# Ambulance_Signal.net
KiCad netlist of a schematic drawn in EAGLE
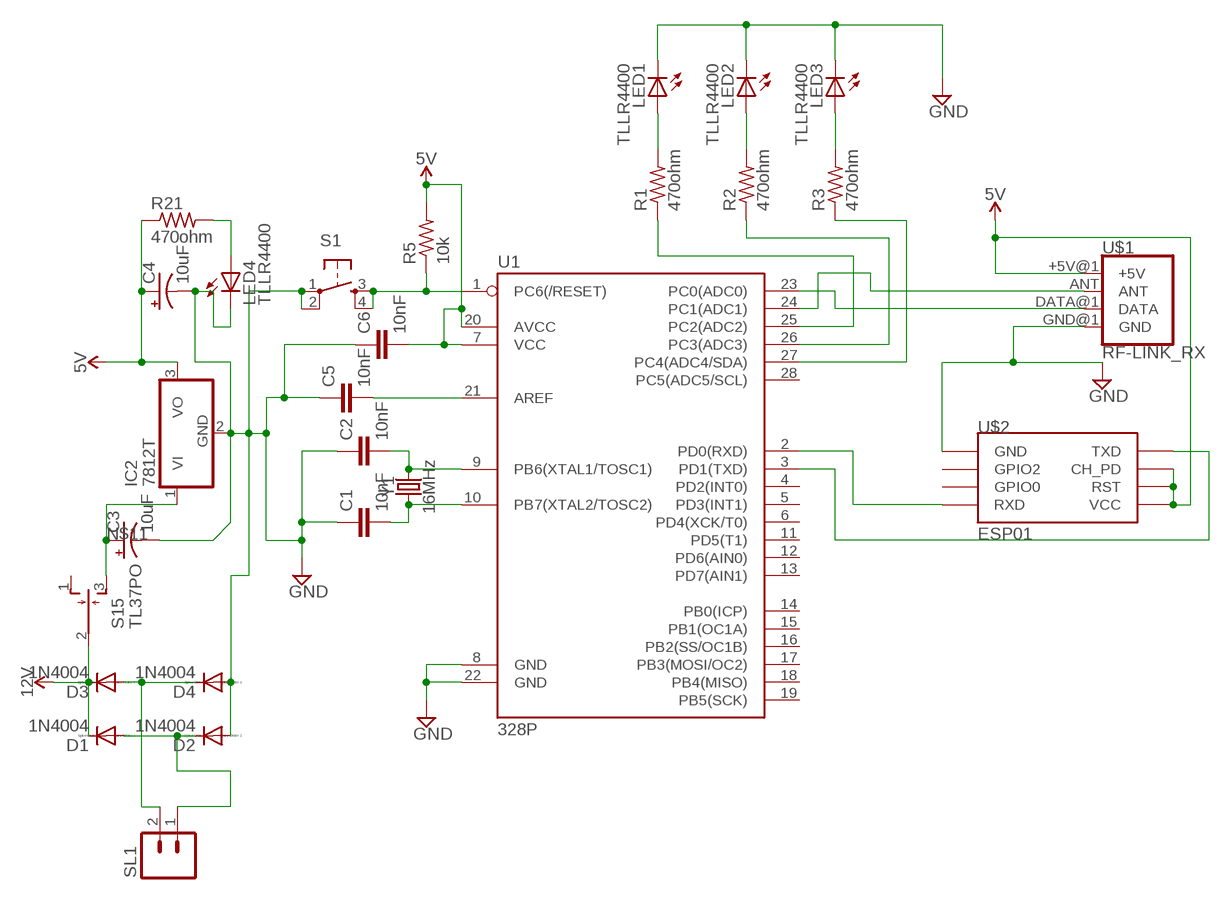
[diagram p0: schematic, sheet 1]

(export (version "E")
  (design (tool "Eeschema 10.0.6"))
  (components
    (comp (ref "C1")
      (value "10nF")
      (footprint "eagle-import:CAP-PTH-10MM")
      (libsource (lib "eagle-import") (part "10NF-PTH-10MM-10000V-1-%"))
    )
    (comp (ref "C2")
      (value "10nF")
      (footprint "eagle-import:CAP-PTH-10MM")
      (libsource (lib "eagle-import") (part "10NF-PTH-10MM-10000V-1-%"))
    )
    (comp (ref "C3")
      (value "10uF")
      (footprint "eagle-import:CPOL-RADIAL-2.5MM-5MM-KIT")
      (libsource (lib "eagle-import") (part "10UF-POLAR-RADIAL-2.5MM-KIT-25V-20%"))
    )
    (comp (ref "C4")
      (value "10uF")
      (footprint "eagle-import:CPOL-RADIAL-2.5MM-5MM-KIT")
      (libsource (lib "eagle-import") (part "10UF-POLAR-RADIAL-2.5MM-KIT-25V-20%"))
    )
    (comp (ref "C5")
      (value "10nF")
      (footprint "eagle-import:CAP-PTH-10MM")
      (libsource (lib "eagle-import") (part "10NF-PTH-10MM-10000V-1-%"))
    )
    (comp (ref "C6")
      (value "10nF")
      (footprint "eagle-import:CAP-PTH-10MM")
      (libsource (lib "eagle-import") (part "10NF-PTH-10MM-10000V-1-%"))
    )
    (comp (ref "D1")
      (value "1N4004")
      (footprint "eagle-import:DO41-10")
      (libsource (lib "eagle-import") (part "1N4004"))
    )
    (comp (ref "D2")
      (value "1N4004")
      (footprint "eagle-import:DO41-10")
      (libsource (lib "eagle-import") (part "1N4004"))
    )
    (comp (ref "D3")
      (value "1N4004")
      (footprint "eagle-import:DO41-10")
      (libsource (lib "eagle-import") (part "1N4004"))
    )
    (comp (ref "D4")
      (value "1N4004")
      (footprint "eagle-import:DO41-10")
      (libsource (lib "eagle-import") (part "1N4004"))
    )
    (comp (ref "IC2")
      (value "7812T")
      (footprint "eagle-import:TO220H")
      (libsource (lib "eagle-import") (part "78T12"))
    )
    (comp (ref "LED1")
      (value "TLLR4400")
      (footprint "eagle-import:LED3MM")
      (fields (field (name "MF") "VISHAY SEMICONDUCTOR"))
      (libsource (lib "eagle-import") (part "TLLR4400"))
    )
    (comp (ref "LED2")
      (value "TLLR4400")
      (footprint "eagle-import:LED3MM")
      (fields (field (name "MF") "VISHAY SEMICONDUCTOR"))
      (libsource (lib "eagle-import") (part "TLLR4400"))
    )
    (comp (ref "LED3")
      (value "TLLR4400")
      (footprint "eagle-import:LED3MM")
      (fields (field (name "MF") "VISHAY SEMICONDUCTOR"))
      (libsource (lib "eagle-import") (part "TLLR4400"))
    )
    (comp (ref "LED4")
      (value "TLLR4400")
      (footprint "eagle-import:LED3MM")
      (fields (field (name "MF") "VISHAY SEMICONDUCTOR"))
      (libsource (lib "eagle-import") (part "TLLR4400"))
    )
    (comp (ref "R1")
      (value "470ohm")
      (footprint "eagle-import:0207_12")
      (libsource (lib "eagle-import") (part "R-US_0207/12"))
    )
    (comp (ref "R2")
      (value "470ohm")
      (footprint "eagle-import:0207_12")
      (libsource (lib "eagle-import") (part "R-US_0207/12"))
    )
    (comp (ref "R3")
      (value "470ohm")
      (footprint "eagle-import:0207_12")
      (libsource (lib "eagle-import") (part "R-US_0207/12"))
    )
    (comp (ref "R5")
      (value "10k")
      (footprint "eagle-import:0207_12")
      (libsource (lib "eagle-import") (part "R-US_0207/12"))
    )
    (comp (ref "R21")
      (value "470ohm")
      (footprint "eagle-import:0207_12")
      (libsource (lib "eagle-import") (part "R-US_0207/12"))
    )
    (comp (ref "S1")
      (value "TAC_SWITCHPTH")
      (footprint "eagle-import:TACTILE-PTH")
      (libsource (lib "eagle-import") (part "TAC_SWITCHPTH"))
    )
    (comp (ref "S15")
      (value "TL37PO")
      (footprint "eagle-import:TL3XPO")
      (libsource (lib "eagle-import") (part "TL37PO"))
    )
    (comp (ref "SL1")
      (value "MA02")
      (footprint "eagle-import:02PA")
      (libsource (lib "eagle-import") (part "MA02"))
    )
    (comp (ref "U$1")
      (value "RF-LINK_RX")
      (footprint "eagle-import:RF-LINK_RX")
      (libsource (lib "eagle-import") (part "RF-LINK_RX"))
    )
    (comp (ref "U$2")
      (value "ESP01")
      (footprint "eagle-import:ESP01")
      (libsource (lib "eagle-import") (part "ESP01"))
    )
    (comp (ref "U1")
      (value "328P")
      (footprint "eagle-import:DIP28")
      (libsource (lib "eagle-import") (part "ATMEGA328P_PDIP"))
    )
    (comp (ref "Y1")
      (value "16MHz")
      (footprint "eagle-import:HC49US")
      (libsource (lib "eagle-import") (part "CRYSTAL-16MHZPTH-HC49US"))
    )
  )
  (nets
    (net (code "1") (name "/N$11") (class "Default")
      (node (ref "C3") (pin "1") (pinfunction "+_1") (pintype "passive"))
      (node (ref "IC2") (pin "1") (pinfunction "VI_1") (pintype "input"))
      (node (ref "S15") (pin "3") (pinfunction "S_3") (pintype "passive"))
    )
    (net (code "2") (name "5V") (class "Default")
      (node (ref "C4") (pin "1") (pinfunction "+_1") (pintype "passive"))
      (node (ref "C6") (pin "2") (pinfunction "2_2") (pintype "passive"))
      (node (ref "IC2") (pin "3") (pinfunction "VO_3") (pintype "passive"))
      (node (ref "R21") (pin "1") (pinfunction "1_1") (pintype "passive"))
      (node (ref "R5") (pin "2") (pinfunction "2_2") (pintype "passive"))
      (node (ref "U$1") (pin "+5V@1") (pinfunction "+5V_+5V@1") (pintype "power_in"))
      (node (ref "U$2") (pin "CH_PD") (pinfunction "CH_PD_CH_PD") (pintype "bidirectional"))
      (node (ref "U$2") (pin "RST") (pinfunction "RST_RST") (pintype "bidirectional"))
      (node (ref "U$2") (pin "VCC") (pinfunction "VCC_VCC") (pintype "bidirectional"))
      (node (ref "U1") (pin "20") (pinfunction "AVCC_20") (pintype "bidirectional"))
      (node (ref "U1") (pin "7") (pinfunction "VCC_7") (pintype "bidirectional"))
    )
    (net (code "3") (name "12V") (class "Default")
      (node (ref "D1") (pin "C") (pinfunction "C_C") (pintype "passive"))
      (node (ref "D3") (pin "C") (pinfunction "C_C") (pintype "passive"))
      (node (ref "S15") (pin "2") (pinfunction "P_2") (pintype "passive"))
    )
    (net (code "4") (name "GND") (class "Default")
      (node (ref "C1") (pin "1") (pinfunction "1_1") (pintype "passive"))
      (node (ref "C2") (pin "1") (pinfunction "1_1") (pintype "passive"))
      (node (ref "C3") (pin "2") (pinfunction "-_2") (pintype "passive"))
      (node (ref "C4") (pin "2") (pinfunction "-_2") (pintype "passive"))
      (node (ref "C5") (pin "1") (pinfunction "1_1") (pintype "passive"))
      (node (ref "C6") (pin "1") (pinfunction "1_1") (pintype "passive"))
      (node (ref "D2") (pin "A") (pinfunction "A_A") (pintype "passive"))
      (node (ref "D4") (pin "A") (pinfunction "A_A") (pintype "passive"))
      (node (ref "IC2") (pin "2") (pinfunction "GND_2") (pintype "passive"))
      (node (ref "LED1") (pin "K") (pinfunction "C_K") (pintype "passive"))
      (node (ref "LED2") (pin "K") (pinfunction "C_K") (pintype "passive"))
      (node (ref "LED3") (pin "K") (pinfunction "C_K") (pintype "passive"))
      (node (ref "LED4") (pin "K") (pinfunction "C_K") (pintype "passive"))
      (node (ref "S1") (pin "1") (pinfunction "1_1") (pintype "passive"))
      (node (ref "S1") (pin "2") (pinfunction "2_2") (pintype "passive"))
      (node (ref "U$1") (pin "GND@1") (pinfunction "GND_GND@1") (pintype "power_in"))
      (node (ref "U$2") (pin "GND") (pinfunction "GND_GND") (pintype "bidirectional"))
      (node (ref "U1") (pin "22") (pinfunction "GND_22") (pintype "bidirectional"))
      (node (ref "U1") (pin "8") (pinfunction "GND_8") (pintype "bidirectional"))
    )
    (net (code "5") (name "Net-(D1-PadA)") (class "Default")
      (node (ref "D1") (pin "A") (pinfunction "A_A") (pintype "passive"))
      (node (ref "D2") (pin "C") (pinfunction "C_C") (pintype "passive"))
      (node (ref "SL1") (pin "1") (pinfunction "1_1") (pintype "passive"))
    )
    (net (code "6") (name "Net-(D3-PadA)") (class "Default")
      (node (ref "D3") (pin "A") (pinfunction "A_A") (pintype "passive"))
      (node (ref "D4") (pin "C") (pinfunction "C_C") (pintype "passive"))
      (node (ref "SL1") (pin "2") (pinfunction "2_2") (pintype "passive"))
    )
    (net (code "7") (name "Net-(LED1-PadA)") (class "Default")
      (node (ref "LED1") (pin "A") (pinfunction "A_A") (pintype "passive"))
      (node (ref "R1") (pin "2") (pinfunction "2_2") (pintype "passive"))
    )
    (net (code "8") (name "Net-(LED2-PadA)") (class "Default")
      (node (ref "LED2") (pin "A") (pinfunction "A_A") (pintype "passive"))
      (node (ref "R2") (pin "2") (pinfunction "2_2") (pintype "passive"))
    )
    (net (code "9") (name "Net-(LED3-PadA)") (class "Default")
      (node (ref "LED3") (pin "A") (pinfunction "A_A") (pintype "passive"))
      (node (ref "R3") (pin "2") (pinfunction "2_2") (pintype "passive"))
    )
    (net (code "10") (name "Net-(LED4-PadA)") (class "Default")
      (node (ref "LED4") (pin "A") (pinfunction "A_A") (pintype "passive"))
      (node (ref "R21") (pin "2") (pinfunction "2_2") (pintype "passive"))
    )
    (net (code "11") (name "Net-(U$1-DATA)") (class "Default")
      (node (ref "U$1") (pin "DATA@1") (pinfunction "DATA_DATA@1") (pintype "input"))
      (node (ref "U1") (pin "23") (pinfunction "PC0(ADC0)_23") (pintype "bidirectional"))
    )
    (net (code "12") (name "Net-(U$2-RXD)") (class "Default")
      (node (ref "U$2") (pin "RX") (pinfunction "RXD_RX") (pintype "bidirectional"))
      (node (ref "U1") (pin "2") (pinfunction "PD0(RXD)_2") (pintype "bidirectional"))
    )
    (net (code "13") (name "Net-(U$2-TXD)") (class "Default")
      (node (ref "U$2") (pin "TX") (pinfunction "TXD_TX") (pintype "bidirectional"))
      (node (ref "U1") (pin "3") (pinfunction "PD1(TXD)_3") (pintype "bidirectional"))
    )
    (net (code "14") (name "Net-(U1-AREF)") (class "Default")
      (node (ref "C5") (pin "2") (pinfunction "2_2") (pintype "passive"))
      (node (ref "U1") (pin "21") (pinfunction "AREF_21") (pintype "bidirectional"))
    )
    (net (code "15") (name "Net-(U1-PB6(XTAL1{slash}TOSC1))") (class "Default")
      (node (ref "C2") (pin "2") (pinfunction "2_2") (pintype "passive"))
      (node (ref "U1") (pin "9") (pinfunction "PB6(XTAL1/TOSC1)_9") (pintype "bidirectional"))
      (node (ref "Y1") (pin "2") (pinfunction "2_2") (pintype "passive"))
    )
    (net (code "16") (name "Net-(U1-PB7(XTAL2{slash}TOSC2))") (class "Default")
      (node (ref "C1") (pin "2") (pinfunction "2_2") (pintype "passive"))
      (node (ref "U1") (pin "10") (pinfunction "PB7(XTAL2/TOSC2)_10") (pintype "bidirectional"))
      (node (ref "Y1") (pin "1") (pinfunction "1_1") (pintype "passive"))
    )
    (net (code "17") (name "Net-(U1-PC1(ADC1))") (class "Default")
      (node (ref "U$1") (pin "ANT") (pinfunction "ANT_ANT") (pintype "passive"))
      (node (ref "U1") (pin "24") (pinfunction "PC1(ADC1)_24") (pintype "bidirectional"))
    )
    (net (code "18") (name "Net-(U1-PC2(ADC2))") (class "Default")
      (node (ref "R1") (pin "1") (pinfunction "1_1") (pintype "passive"))
      (node (ref "U1") (pin "25") (pinfunction "PC2(ADC2)_25") (pintype "bidirectional"))
    )
    (net (code "19") (name "Net-(U1-PC3(ADC3))") (class "Default")
      (node (ref "R2") (pin "1") (pinfunction "1_1") (pintype "passive"))
      (node (ref "U1") (pin "26") (pinfunction "PC3(ADC3)_26") (pintype "bidirectional"))
    )
    (net (code "20") (name "Net-(U1-PC4(ADC4{slash}SDA))") (class "Default")
      (node (ref "R3") (pin "1") (pinfunction "1_1") (pintype "passive"))
      (node (ref "U1") (pin "27") (pinfunction "PC4(ADC4/SDA)_27") (pintype "bidirectional"))
    )
    (net (code "21") (name "Net-(U1-PC6({slash}RESET))") (class "Default")
      (node (ref "R5") (pin "1") (pinfunction "1_1") (pintype "passive"))
      (node (ref "S1") (pin "3") (pinfunction "3_3") (pintype "passive"))
      (node (ref "S1") (pin "4") (pinfunction "4_4") (pintype "passive"))
      (node (ref "U1") (pin "1") (pinfunction "PC6(/RESET)_1") (pintype "bidirectional"))
    )
    (net (code "22") (name "unconnected-(S15-O-Pad1)") (class "Default")
      (node (ref "S15") (pin "1") (pinfunction "O_1") (pintype "passive"))
    )
    (net (code "23") (name "unconnected-(U$2-PadGPIO0)") (class "Default")
      (node (ref "U$2") (pin "GPIO0") (pinfunction "GPIO0_GPIO0") (pintype "bidirectional"))
    )
    (net (code "24") (name "unconnected-(U$2-PadGPIO2)") (class "Default")
      (node (ref "U$2") (pin "GPIO2") (pinfunction "GPIO2_GPIO2") (pintype "bidirectional"))
    )
    (net (code "25") (name "unconnected-(U1-PB0(ICP)-Pad14)") (class "Default")
      (node (ref "U1") (pin "14") (pinfunction "PB0(ICP)_14") (pintype "bidirectional"))
    )
    (net (code "26") (name "unconnected-(U1-PB1(OC1A)-Pad15)") (class "Default")
      (node (ref "U1") (pin "15") (pinfunction "PB1(OC1A)_15") (pintype "bidirectional"))
    )
    (net (code "27") (name "unconnected-(U1-PB2(SS{slash}OC1B)-Pad16)") (class "Default")
      (node (ref "U1") (pin "16") (pinfunction "PB2(SS/OC1B)_16") (pintype "bidirectional"))
    )
    (net (code "28") (name "unconnected-(U1-PB3(MOSI{slash}OC2)-Pad17)") (class "Default")
      (node (ref "U1") (pin "17") (pinfunction "PB3(MOSI/OC2)_17") (pintype "bidirectional"))
    )
    (net (code "29") (name "unconnected-(U1-PB4(MISO)-Pad18)") (class "Default")
      (node (ref "U1") (pin "18") (pinfunction "PB4(MISO)_18") (pintype "bidirectional"))
    )
    (net (code "30") (name "unconnected-(U1-PB5(SCK)-Pad19)") (class "Default")
      (node (ref "U1") (pin "19") (pinfunction "PB5(SCK)_19") (pintype "bidirectional"))
    )
    (net (code "31") (name "unconnected-(U1-PC5(ADC5{slash}SCL)-Pad28)") (class "Default")
      (node (ref "U1") (pin "28") (pinfunction "PC5(ADC5/SCL)_28") (pintype "bidirectional"))
    )
    (net (code "32") (name "unconnected-(U1-PD2(INT0)-Pad4)") (class "Default")
      (node (ref "U1") (pin "4") (pinfunction "PD2(INT0)_4") (pintype "bidirectional"))
    )
    (net (code "33") (name "unconnected-(U1-PD3(INT1)-Pad5)") (class "Default")
      (node (ref "U1") (pin "5") (pinfunction "PD3(INT1)_5") (pintype "bidirectional"))
    )
    (net (code "34") (name "unconnected-(U1-PD4(XCK{slash}T0)-Pad6)") (class "Default")
      (node (ref "U1") (pin "6") (pinfunction "PD4(XCK/T0)_6") (pintype "bidirectional"))
    )
    (net (code "35") (name "unconnected-(U1-PD5(T1)-Pad11)") (class "Default")
      (node (ref "U1") (pin "11") (pinfunction "PD5(T1)_11") (pintype "bidirectional"))
    )
    (net (code "36") (name "unconnected-(U1-PD6(AIN0)-Pad12)") (class "Default")
      (node (ref "U1") (pin "12") (pinfunction "PD6(AIN0)_12") (pintype "bidirectional"))
    )
    (net (code "37") (name "unconnected-(U1-PD7(AIN1)-Pad13)") (class "Default")
      (node (ref "U1") (pin "13") (pinfunction "PD7(AIN1)_13") (pintype "bidirectional"))
    )
  )
)
